# ProPrj_cyrus_2026-03-31.net
KiCad netlist of a schematic drawn in EasyEDA Pro
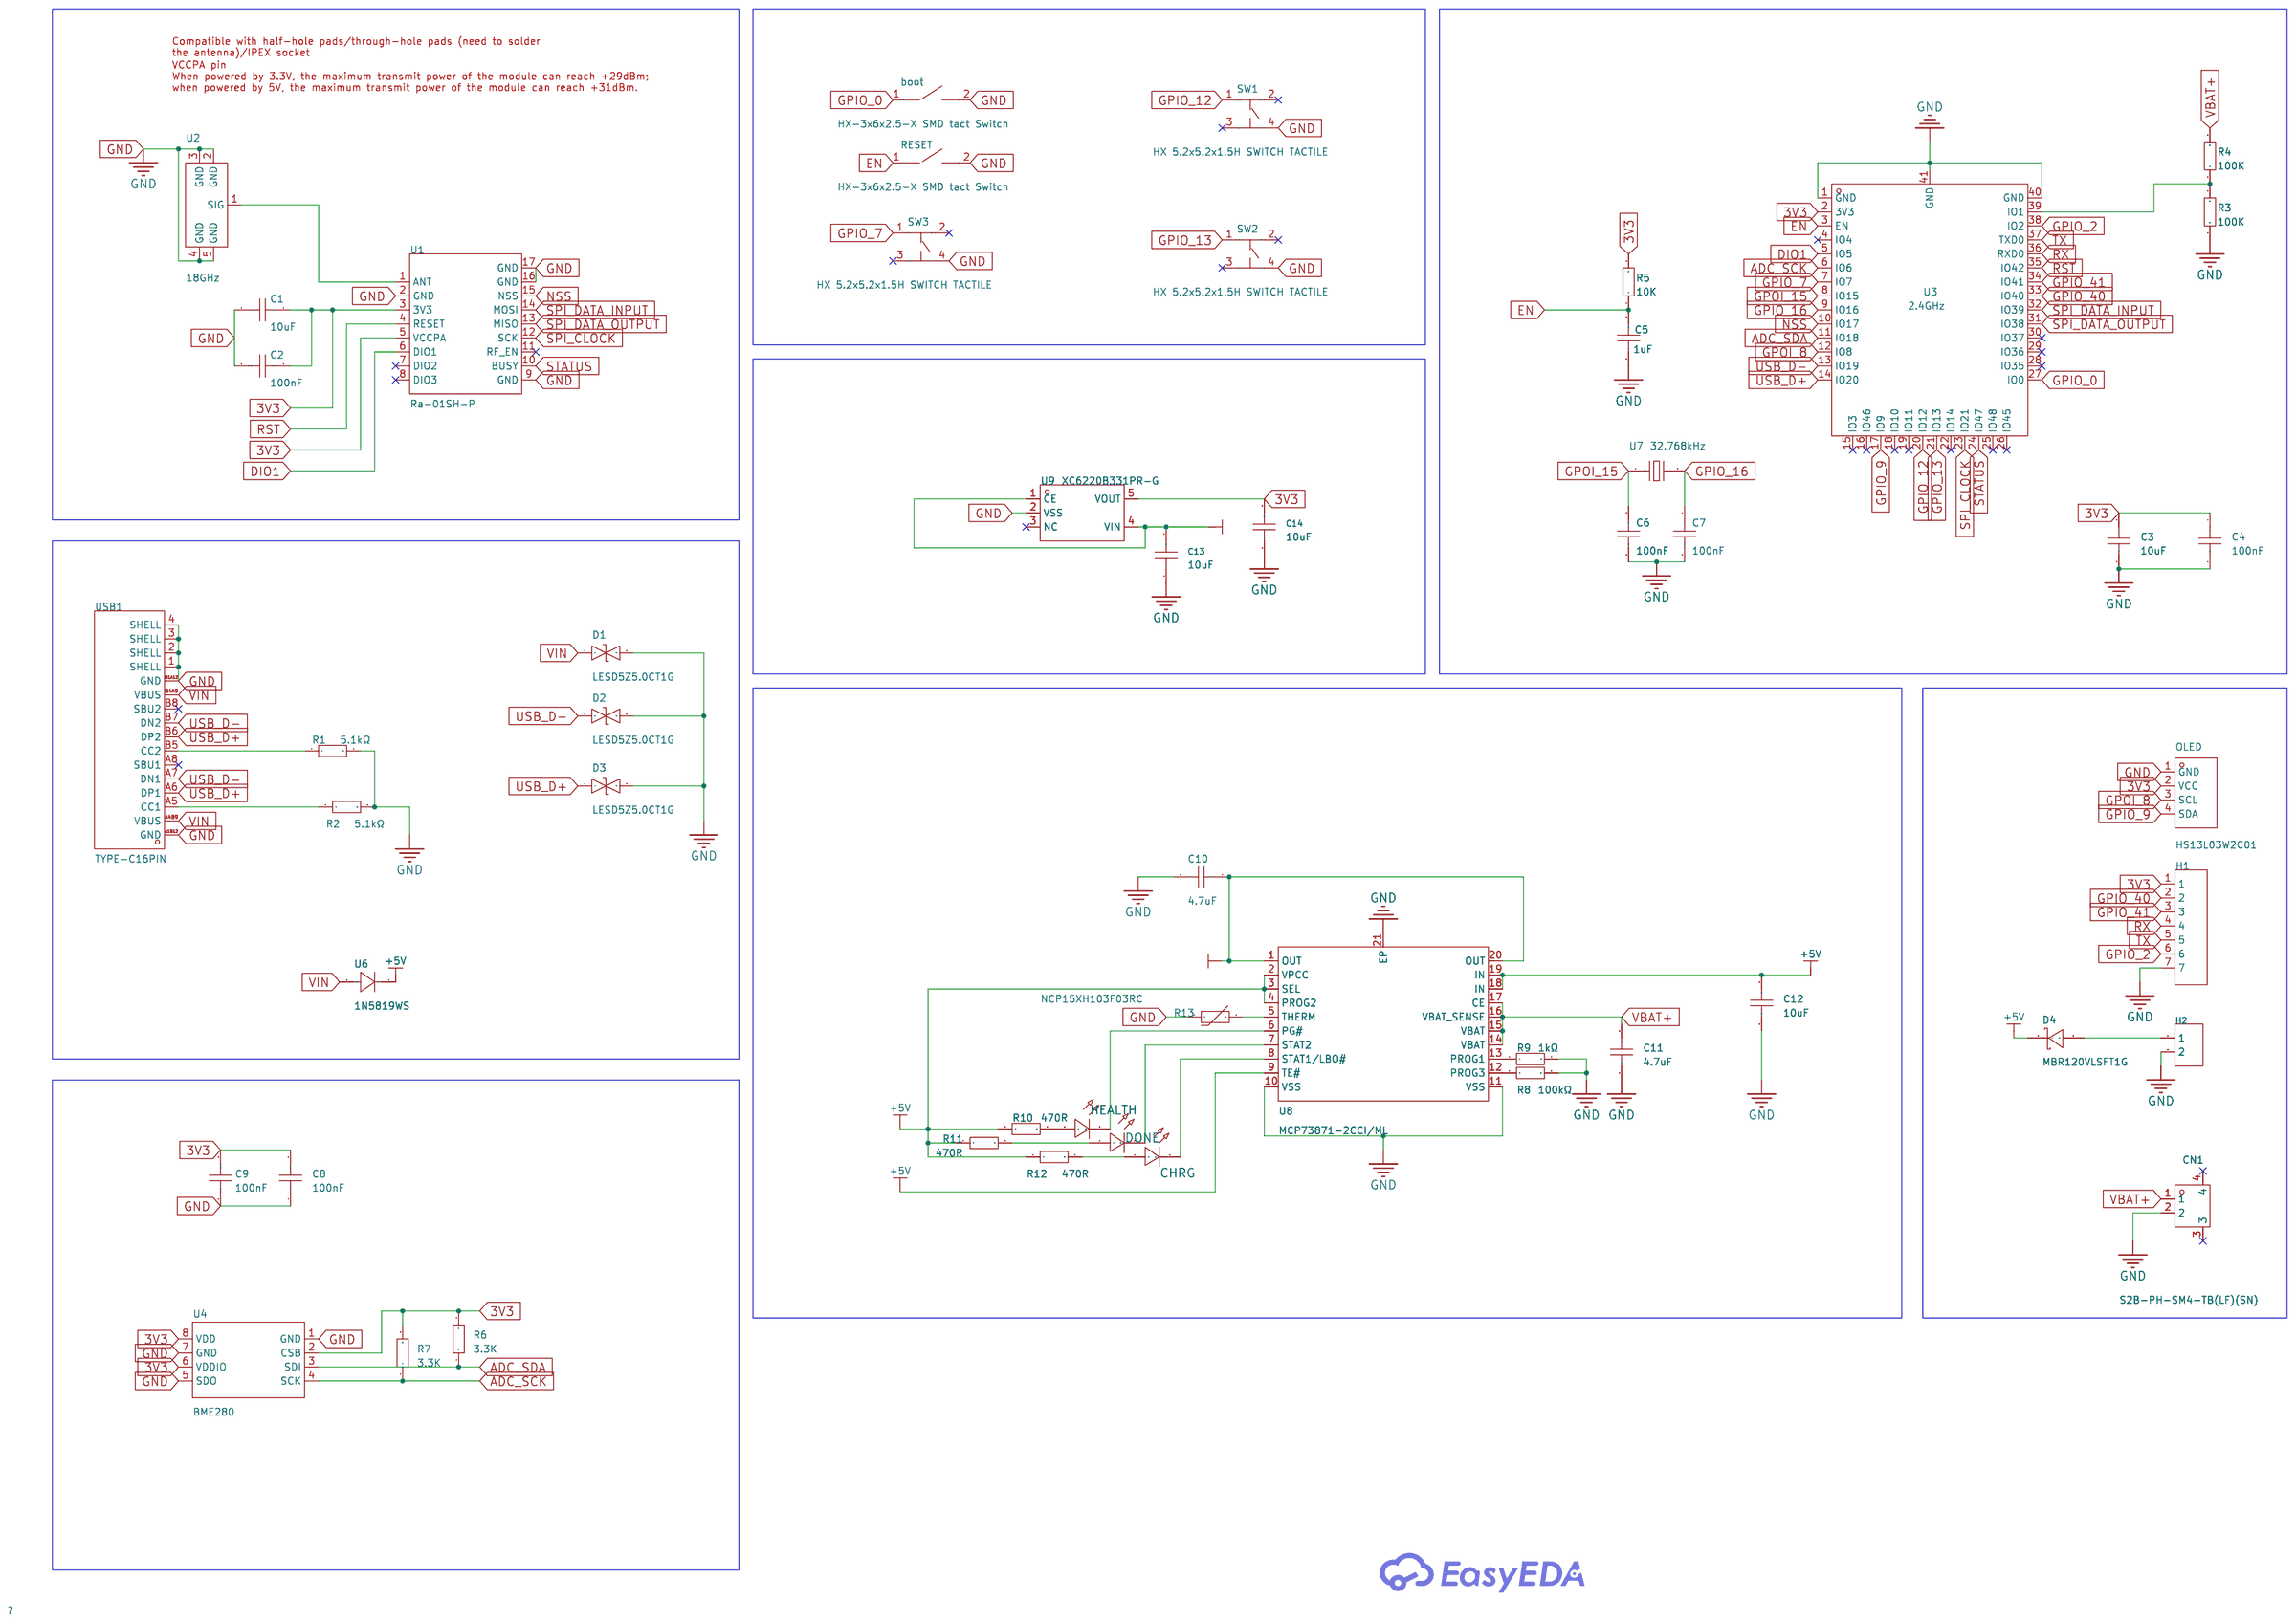
[diagram p0: schematic sheet]

(export (version "E")
  (design (tool "Eeschema 10.0.6"))
  (components
    (comp (ref "boot")
      (value "HX-3x6x2.5-X SMD tact Switch")
      (footprint "easyedapro:SW-SMD_HX-3X6X2.5-X")
      (fields (field (name "Manufacturer") "hanxia(韩下)"))
      (libsource (lib "easyedapro") (part "HX-3X6X2.5-X SMD TACT SWITCH"))
    )
    (comp (ref "C1")
      (value "10uF")
      (footprint "easyedapro:C0603")
      (libsource (lib "easyedapro") (part "CAP"))
    )
    (comp (ref "C2")
      (value "100nF")
      (footprint "easyedapro:C0603")
      (libsource (lib "easyedapro") (part "CAP"))
    )
    (comp (ref "C3")
      (value "10uF")
      (footprint "easyedapro:C0603")
      (libsource (lib "easyedapro") (part "CAP"))
    )
    (comp (ref "C4")
      (value "100nF")
      (footprint "easyedapro:C0603")
      (libsource (lib "easyedapro") (part "CAP"))
    )
    (comp (ref "C5") (value "1uF") (footprint "easyedapro:C0603") (libsource (lib "easyedapro") (part "CAP")))
    (comp (ref "C6")
      (value "100nF")
      (footprint "easyedapro:C0603")
      (libsource (lib "easyedapro") (part "CAP"))
    )
    (comp (ref "C7")
      (value "100nF")
      (footprint "easyedapro:C0603")
      (libsource (lib "easyedapro") (part "CAP"))
    )
    (comp (ref "C8")
      (value "100nF")
      (footprint "easyedapro:C0603")
      (description "Capacitance:100nF Tolerance:±10% Tolerance:±10% Voltage Rating:50V Temperature Coefficient:X7R")
      (fields
        (field (name "Manufacturer Part") "CC0603KRX7R9BB104")
        (field (name "Manufacturer") "YAGEO(国巨)")
      )
      (libsource (lib "easyedapro") (part "CC0603KRX7R9BB104"))
    )
    (comp (ref "C9")
      (value "100nF")
      (footprint "easyedapro:C0603")
      (description "Capacitance:100nF Tolerance:±10% Tolerance:±10% Voltage Rating:50V Temperature Coefficient:X7R")
      (fields
        (field (name "Manufacturer Part") "CC0603KRX7R9BB104")
        (field (name "Manufacturer") "YAGEO(国巨)")
      )
      (libsource (lib "easyedapro") (part "CC0603KRX7R9BB104"))
    )
    (comp (ref "C10")
      (value "4.7uF")
      (footprint "easyedapro:C0402")
      (description "Capacitance:4.7uF Tolerance:±20% Tolerance:±20% Voltage Rating:10V Temperature Coefficient:X5R")
      (fields
        (field (name "Manufacturer Part") "CL05A475MP5NRNC")
        (field (name "Manufacturer") "SAMSUNG(三星)")
      )
      (libsource (lib "easyedapro") (part "CL05A475MP5NRNC"))
    )
    (comp (ref "C11")
      (value "4.7uF")
      (footprint "easyedapro:C0402")
      (description "Capacitance:4.7uF Tolerance:±20% Tolerance:±20% Voltage Rating:10V Temperature Coefficient:X5R")
      (fields
        (field (name "Manufacturer Part") "CL05A475MP5NRNC")
        (field (name "Manufacturer") "SAMSUNG(三星)")
      )
      (libsource (lib "easyedapro") (part "CL05A475MP5NRNC"))
    )
    (comp (ref "C12")
      (value "10uF")
      (footprint "easyedapro:C0402")
      (description "Capacitance:10uF Tolerance:±20% Tolerance:±20% Voltage Rating:10V Temperature Coefficient:X5R")
      (fields
        (field (name "Manufacturer Part") "CL05A106MP5NUNC")
        (field (name "Manufacturer") "SAMSUNG(三星)")
      )
      (libsource (lib "easyedapro") (part "CL05A106MP5NUNC_C315248"))
    )
    (comp (ref "C13")
      (value "10uF")
      (footprint "easyedapro:C0603")
      (description "Capacitance:10uF Tolerance:±20% Tolerance:±20% Voltage Rating:25V Temperature Coefficient:X5R")
      (fields
        (field (name "Manufacturer Part") "CL10A106MA8NRNC")
        (field (name "Manufacturer") "SAMSUNG(三星)")
      )
      (libsource (lib "easyedapro") (part "CL10A106MA8NRNC"))
    )
    (comp (ref "C14")
      (value "10uF")
      (footprint "easyedapro:C0603")
      (description "Capacitance:10uF Tolerance:±20% Tolerance:±20% Voltage Rating:25V Temperature Coefficient:X5R")
      (fields
        (field (name "Manufacturer Part") "CL10A106MA8NRNC")
        (field (name "Manufacturer") "SAMSUNG(三星)")
      )
      (libsource (lib "easyedapro") (part "CL10A106MA8NRNC"))
    )
    (comp (ref "CHRG")
      (value "~")
      (footprint "easyedapro:LED0603-R-RD")
      (libsource (lib "easyedapro") (part "LED_R"))
    )
    (comp (ref "CN1")
      (value "S2B-PH-SM4-TB(LF)(SN)")
      (footprint "easyedapro:CONN-SMD_P2.00_S2B-PH-SM4-TB-LF-SN")
      (fields (field (name "Manufacturer") "JST"))
      (libsource (lib "easyedapro") (part "S2B-PH-SM4-TB(LF)(SN)"))
    )
    (comp (ref "D1")
      (value "LESD5Z5.0CT1G")
      (footprint "easyedapro:SOD-523_L1.2-W0.8-LS1.6-BI")
      (fields (field (name "Manufacturer") "LRC(乐山无线电)"))
      (libsource (lib "easyedapro") (part "LESD5Z5.0CT1G"))
    )
    (comp (ref "D2")
      (value "LESD5Z5.0CT1G")
      (footprint "easyedapro:SOD-523_L1.2-W0.8-LS1.6-BI")
      (fields (field (name "Manufacturer") "LRC(乐山无线电)"))
      (libsource (lib "easyedapro") (part "LESD5Z5.0CT1G"))
    )
    (comp (ref "D3")
      (value "LESD5Z5.0CT1G")
      (footprint "easyedapro:SOD-523_L1.2-W0.8-LS1.6-BI")
      (fields (field (name "Manufacturer") "LRC(乐山无线电)"))
      (libsource (lib "easyedapro") (part "LESD5Z5.0CT1G"))
    )
    (comp (ref "D4")
      (value "MBR120VLSFT1G")
      (footprint "easyedapro:SOD-123F_L2.8-W1.8-LS3.7-RD")
      (fields (field (name "Manufacturer") "onsemi(安森美)"))
      (libsource (lib "easyedapro") (part "MBR120VLSFT1G"))
    )
    (comp (ref "DONE")
      (value "~")
      (footprint "easyedapro:LED0603-R-RD")
      (libsource (lib "easyedapro") (part "LED_R"))
    )
    (comp (ref "H1")
      (value "~")
      (footprint "easyedapro:HDR-TH_7P-P2.54-V-F")
      (libsource (lib "easyedapro") (part "220S-1*7P H=8.5MM Ytype Gold-plated"))
    )
    (comp (ref "H2")
      (value "~")
      (footprint "easyedapro:HDR-TH_2P-P2.54-V-F")
      (libsource (lib "easyedapro") (part "Header-Female-2.54_1x2"))
    )
    (comp (ref "HEALTH")
      (value "~")
      (footprint "easyedapro:LED0603-R-RD")
      (libsource (lib "easyedapro") (part "LED_R"))
    )
    (comp (ref "OLED")
      (value "HS13L03W2C01")
      (footprint "easyedapro:OLED-TH_L35.4-W33.5_HS13L03W2C01")
      (fields (field (name "Manufacturer") "HS(汉昇)"))
      (libsource (lib "easyedapro") (part "HS13L03W2C01"))
    )
    (comp (ref "R1")
      (value "5.1kΩ")
      (footprint "easyedapro:R0603")
      (libsource (lib "easyedapro") (part "Res"))
    )
    (comp (ref "R2")
      (value "5.1kΩ")
      (footprint "easyedapro:R0603")
      (libsource (lib "easyedapro") (part "Res"))
    )
    (comp (ref "R3")
      (value "100K")
      (footprint "easyedapro:R0603")
      (libsource (lib "easyedapro") (part "Res"))
    )
    (comp (ref "R4")
      (value "100K")
      (footprint "easyedapro:R0603")
      (libsource (lib "easyedapro") (part "Res"))
    )
    (comp (ref "R5") (value "10K") (footprint "easyedapro:R0603") (libsource (lib "easyedapro") (part "Res")))
    (comp (ref "R6")
      (value "3.3K")
      (footprint "easyedapro:R0603")
      (libsource (lib "easyedapro") (part "Res"))
    )
    (comp (ref "R7")
      (value "3.3K")
      (footprint "easyedapro:R0603")
      (libsource (lib "easyedapro") (part "Res"))
    )
    (comp (ref "R8")
      (value "100kΩ")
      (footprint "easyedapro:R0603")
      (fields
        (field (name "Manufacturer Part") "0603WAF1003T5E")
        (field (name "Manufacturer") "UNI-ROYAL(厚声)")
      )
      (libsource (lib "easyedapro") (part "0603WAF1003T5E"))
    )
    (comp (ref "R9")
      (value "1kΩ")
      (footprint "easyedapro:R0402")
      (fields
        (field (name "Manufacturer Part") "0402WGF1001TCE")
        (field (name "Manufacturer") "UNI-ROYAL(厚声)")
      )
      (libsource (lib "easyedapro") (part "0402WGF1001TCE"))
    )
    (comp (ref "R10")
      (value "470R")
      (footprint "easyedapro:R0603")
      (libsource (lib "easyedapro") (part "Res"))
    )
    (comp (ref "R11")
      (value "470R")
      (footprint "easyedapro:R0603")
      (libsource (lib "easyedapro") (part "Res"))
    )
    (comp (ref "R12")
      (value "470R")
      (footprint "easyedapro:R0603")
      (libsource (lib "easyedapro") (part "Res"))
    )
    (comp (ref "R13")
      (value "NCP15XH103F03RC")
      (footprint "easyedapro:R0402")
      (fields (field (name "Manufacturer") "muRata(村田)"))
      (libsource (lib "easyedapro") (part "NCP15XH103F03RC"))
    )
    (comp (ref "RESET")
      (value "HX-3x6x2.5-X SMD tact Switch")
      (footprint "easyedapro:SW-SMD_HX-3X6X2.5-X")
      (fields (field (name "Manufacturer") "hanxia(韩下)"))
      (libsource (lib "easyedapro") (part "HX-3X6X2.5-X SMD TACT SWITCH"))
    )
    (comp (ref "SW1")
      (value "HX 5.2x5.2x1.5H SWITCH TACTILE")
      (footprint "easyedapro:SW-SMD_4P-L5.2-W5.2-P3.7-LS6.4-1")
      (fields (field (name "Manufacturer") "hanxia(韩下)"))
      (libsource (lib "easyedapro") (part "HX 5.2X5.2X1.5H SWITCH TACTILE"))
    )
    (comp (ref "SW2")
      (value "HX 5.2x5.2x1.5H SWITCH TACTILE")
      (footprint "easyedapro:SW-SMD_4P-L5.2-W5.2-P3.7-LS6.4-1")
      (fields (field (name "Manufacturer") "hanxia(韩下)"))
      (libsource (lib "easyedapro") (part "HX 5.2X5.2X1.5H SWITCH TACTILE"))
    )
    (comp (ref "SW3")
      (value "HX 5.2x5.2x1.5H SWITCH TACTILE")
      (footprint "easyedapro:SW-SMD_4P-L5.2-W5.2-P3.7-LS6.4-1")
      (fields (field (name "Manufacturer") "hanxia(韩下)"))
      (libsource (lib "easyedapro") (part "HX 5.2X5.2X1.5H SWITCH TACTILE"))
    )
    (comp (ref "U1")
      (value "Ra-01SH-P")
      (footprint "easyedapro:COMM-SMD_17P-L17.0-W16.0-P2.00_RA-01S-P")
      (fields (field (name "Manufacturer") "Ai-Thinker(安信可)"))
      (libsource (lib "easyedapro") (part "RA-01SH-P"))
    )
    (comp (ref "U2")
      (value "18GHz")
      (footprint "easyedapro:SMA-SMD_HJ-SMA076")
      (fields (field (name "Manufacturer Part") "142-0701-801") (field (name "Manufacturer") "belfuse"))
      (libsource (lib "easyedapro") (part "142-0701-801"))
    )
    (comp (ref "U3")
      (value "2.4GHz")
      (footprint "easyedapro:WIRELM-SMD_ESP32-S3-WROOM-1")
      (fields
        (field (name "Manufacturer Part") "ESP32-S3-WROOM-1-N8R8")
        (field (name "Manufacturer") "ESPRESSIF(乐鑫)")
      )
      (libsource (lib "easyedapro") (part "ESP32-S3-WROOM-1(N8R8)"))
    )
    (comp (ref "U4")
      (value "BME280")
      (footprint "easyedapro:LGA-8_BME280_BL")
      (fields (field (name "Manufacturer") "Bosch(博世)"))
      (libsource (lib "easyedapro") (part "BME280"))
    )
    (comp (ref "U6")
      (value "1N5819WS")
      (footprint "easyedapro:SOD-323_L1.8-W1.3-LS2.5-RD")
      (fields (field (name "Manufacturer") "HXY MOSFET(华轩阳电子)"))
      (libsource (lib "easyedapro") (part "1N5819WS_C5451629"))
    )
    (comp (ref "U7")
      (value "32.768kHz")
      (footprint "easyedapro:CRYSTAL-SMD_L3.2-W1.5-1")
      (fields (field (name "Manufacturer Part") "RN32768016") (field (name "Manufacturer") "TROQ(创捷)"))
      (libsource (lib "easyedapro") (part "RN32768016"))
    )
    (comp (ref "U8")
      (value "MCP73871-2CCI/ML")
      (footprint "easyedapro:QFN-20_L4.0-W4.0-P0.50-BL-EP2.7")
      (fields (field (name "Manufacturer") "MICROCHIP(美国微芯)"))
      (libsource (lib "easyedapro") (part "MCP73871-2CCI/ML"))
    )
    (comp (ref "U9")
      (value "XC6220B331PR-G")
      (footprint "easyedapro:SOT-89-5_L4.5-W2.5-P1.50-LS4.4-BR")
      (fields (field (name "Manufacturer") "TOREX(特瑞仕)"))
      (libsource (lib "easyedapro") (part "XC6220B331PR-G"))
    )
    (comp (ref "USB1")
      (value "TYPE-C16PIN")
      (footprint "easyedapro:USB-C-SMD_TYPE-C16PIN")
      (fields (field (name "Manufacturer") "SHOU HAN(首韩)"))
      (libsource (lib "easyedapro") (part "TYPE-C16PIN"))
    )
  )
  (nets
    (net (code "1") (name "+5V") (class "Default")
      (node (ref "C12") (pin "2") (pinfunction "2_2") (pintype "unspecified"))
      (node (ref "D4") (pin "1") (pinfunction "K_1") (pintype "unspecified"))
      (node (ref "R10") (pin "1") (pinfunction "1_1") (pintype "input"))
      (node (ref "R11") (pin "1") (pinfunction "1_1") (pintype "input"))
      (node (ref "R12") (pin "1") (pinfunction "1_1") (pintype "input"))
      (node (ref "U6") (pin "1") (pinfunction "K_1") (pintype "unspecified"))
      (node (ref "U8") (pin "18") (pinfunction "IN_18") (pintype "unspecified"))
      (node (ref "U8") (pin "19") (pinfunction "IN_19") (pintype "unspecified"))
      (node (ref "U8") (pin "2") (pinfunction "VPCC_2") (pintype "unspecified"))
      (node (ref "U8") (pin "3") (pinfunction "SEL_3") (pintype "unspecified"))
      (node (ref "U8") (pin "4") (pinfunction "PROG2_4") (pintype "unspecified"))
      (node (ref "U8") (pin "9") (pinfunction "TE#_9") (pintype "unspecified"))
    )
    (net (code "2") (name "3V3") (class "Default")
      (node (ref "C1") (pin "1") (pinfunction "1_1") (pintype "input"))
      (node (ref "C14") (pin "2") (pinfunction "2_2") (pintype "input"))
      (node (ref "C2") (pin "1") (pinfunction "1_1") (pintype "input"))
      (node (ref "C3") (pin "1") (pinfunction "1_1") (pintype "input"))
      (node (ref "C4") (pin "1") (pinfunction "1_1") (pintype "input"))
      (node (ref "C8") (pin "2") (pinfunction "2_2") (pintype "unspecified"))
      (node (ref "C9") (pin "2") (pinfunction "2_2") (pintype "unspecified"))
      (node (ref "H1") (pin "1") (pinfunction "1_1") (pintype "unspecified"))
      (node (ref "OLED") (pin "2") (pinfunction "VCC_2") (pintype "unspecified"))
      (node (ref "R5") (pin "2") (pinfunction "2_2") (pintype "input"))
      (node (ref "R6") (pin "2") (pinfunction "2_2") (pintype "input"))
      (node (ref "R7") (pin "2") (pinfunction "2_2") (pintype "input"))
      (node (ref "U1") (pin "3") (pinfunction "3V3_3") (pintype "unspecified"))
      (node (ref "U1") (pin "5") (pinfunction "VCCPA_5") (pintype "unspecified"))
      (node (ref "U3") (pin "2") (pinfunction "3V3_2") (pintype "unspecified"))
      (node (ref "U4") (pin "2") (pinfunction "CSB_2") (pintype "unspecified"))
      (node (ref "U4") (pin "6") (pinfunction "VDDIO_6") (pintype "unspecified"))
      (node (ref "U4") (pin "8") (pinfunction "VDD_8") (pintype "unspecified"))
      (node (ref "U9") (pin "5") (pinfunction "VOUT_5") (pintype "unspecified"))
    )
    (net (code "3") (name "ADC_SCK") (class "Default")
      (node (ref "R7") (pin "1") (pinfunction "1_1") (pintype "input"))
      (node (ref "U3") (pin "6") (pinfunction "IO6_6") (pintype "unspecified"))
      (node (ref "U4") (pin "4") (pinfunction "SCK_4") (pintype "unspecified"))
    )
    (net (code "4") (name "ADC_SDA") (class "Default")
      (node (ref "R6") (pin "1") (pinfunction "1_1") (pintype "input"))
      (node (ref "U3") (pin "11") (pinfunction "IO18_11") (pintype "unspecified"))
      (node (ref "U4") (pin "3") (pinfunction "SDI_3") (pintype "unspecified"))
    )
    (net (code "5") (name "DIO1") (class "Default")
      (node (ref "U1") (pin "6") (pinfunction "DIO1_6") (pintype "unspecified"))
      (node (ref "U3") (pin "5") (pinfunction "IO5_5") (pintype "unspecified"))
    )
    (net (code "6") (name "EN") (class "Default")
      (node (ref "C5") (pin "1") (pinfunction "1_1") (pintype "input"))
      (node (ref "R5") (pin "1") (pinfunction "1_1") (pintype "input"))
      (node (ref "RESET") (pin "1") (pinfunction "1_1") (pintype "unspecified"))
      (node (ref "U3") (pin "3") (pinfunction "EN_3") (pintype "unspecified"))
    )
    (net (code "7") (name "GND") (class "Default")
      (node (ref "C1") (pin "2") (pinfunction "2_2") (pintype "input"))
      (node (ref "C10") (pin "1") (pinfunction "1_1") (pintype "unspecified"))
      (node (ref "C11") (pin "1") (pinfunction "1_1") (pintype "unspecified"))
      (node (ref "C12") (pin "1") (pinfunction "1_1") (pintype "unspecified"))
      (node (ref "C13") (pin "1") (pinfunction "1_1") (pintype "input"))
      (node (ref "C14") (pin "1") (pinfunction "1_1") (pintype "input"))
      (node (ref "C2") (pin "2") (pinfunction "2_2") (pintype "input"))
      (node (ref "C3") (pin "2") (pinfunction "2_2") (pintype "input"))
      (node (ref "C4") (pin "2") (pinfunction "2_2") (pintype "input"))
      (node (ref "C5") (pin "2") (pinfunction "2_2") (pintype "input"))
      (node (ref "C6") (pin "2") (pinfunction "2_2") (pintype "input"))
      (node (ref "C7") (pin "2") (pinfunction "2_2") (pintype "input"))
      (node (ref "C8") (pin "1") (pinfunction "1_1") (pintype "unspecified"))
      (node (ref "C9") (pin "1") (pinfunction "1_1") (pintype "unspecified"))
      (node (ref "CN1") (pin "2") (pinfunction "2_2") (pintype "unspecified"))
      (node (ref "D1") (pin "2") (pinfunction "2_2") (pintype "unspecified"))
      (node (ref "D2") (pin "2") (pinfunction "2_2") (pintype "unspecified"))
      (node (ref "D3") (pin "2") (pinfunction "2_2") (pintype "unspecified"))
      (node (ref "H1") (pin "7") (pinfunction "7_7") (pintype "unspecified"))
      (node (ref "H2") (pin "2") (pinfunction "2_2") (pintype "input"))
      (node (ref "OLED") (pin "1") (pinfunction "GND_1") (pintype "unspecified"))
      (node (ref "R1") (pin "2") (pinfunction "2_2") (pintype "input"))
      (node (ref "R13") (pin "1") (pinfunction "1_1") (pintype "input"))
      (node (ref "R2") (pin "2") (pinfunction "2_2") (pintype "input"))
      (node (ref "R3") (pin "1") (pinfunction "1_1") (pintype "input"))
      (node (ref "R8") (pin "2") (pinfunction "2_2") (pintype "input"))
      (node (ref "R9") (pin "2") (pinfunction "2_2") (pintype "input"))
      (node (ref "RESET") (pin "2") (pinfunction "2_2") (pintype "unspecified"))
      (node (ref "SW1") (pin "4") (pinfunction "4_4") (pintype "unspecified"))
      (node (ref "SW2") (pin "4") (pinfunction "4_4") (pintype "unspecified"))
      (node (ref "SW3") (pin "4") (pinfunction "4_4") (pintype "unspecified"))
      (node (ref "U1") (pin "16") (pinfunction "GND_16") (pintype "unspecified"))
      (node (ref "U1") (pin "17") (pinfunction "GND_17") (pintype "unspecified"))
      (node (ref "U1") (pin "2") (pinfunction "GND_2") (pintype "unspecified"))
      (node (ref "U1") (pin "9") (pinfunction "GND_9") (pintype "unspecified"))
      (node (ref "U2") (pin "2") (pinfunction "GND_2") (pintype "unspecified"))
      (node (ref "U2") (pin "3") (pinfunction "GND_3") (pintype "unspecified"))
      (node (ref "U2") (pin "4") (pinfunction "GND_4") (pintype "unspecified"))
      (node (ref "U2") (pin "5") (pinfunction "GND_5") (pintype "unspecified"))
      (node (ref "U3") (pin "1") (pinfunction "GND_1") (pintype "unspecified"))
      (node (ref "U3") (pin "40") (pinfunction "GND_40") (pintype "unspecified"))
      (node (ref "U3") (pin "41") (pinfunction "GND_41") (pintype "unspecified"))
      (node (ref "U4") (pin "1") (pinfunction "GND_1") (pintype "unspecified"))
      (node (ref "U4") (pin "5") (pinfunction "SDO_5") (pintype "unspecified"))
      (node (ref "U4") (pin "7") (pinfunction "GND_7") (pintype "unspecified"))
      (node (ref "U8") (pin "10") (pinfunction "VSS_10") (pintype "unspecified"))
      (node (ref "U8") (pin "11") (pinfunction "VSS_11") (pintype "unspecified"))
      (node (ref "U8") (pin "21") (pinfunction "EP_21") (pintype "unspecified"))
      (node (ref "U9") (pin "2") (pinfunction "VSS_2") (pintype "unspecified"))
      (node (ref "USB1") (pin "1") (pinfunction "SHELL_1") (pintype "unspecified"))
      (node (ref "USB1") (pin "2") (pinfunction "SHELL_2") (pintype "unspecified"))
      (node (ref "USB1") (pin "3") (pinfunction "SHELL_3") (pintype "unspecified"))
      (node (ref "USB1") (pin "4") (pinfunction "SHELL_4") (pintype "unspecified"))
      (node (ref "USB1") (pin "A1B12") (pinfunction "GND_A1B12") (pintype "unspecified"))
      (node (ref "USB1") (pin "B1A12") (pinfunction "GND_B1A12") (pintype "unspecified"))
      (node (ref "boot") (pin "2") (pinfunction "2_2") (pintype "unspecified"))
    )
    (net (code "8") (name "GPIO_0") (class "Default")
      (node (ref "U3") (pin "27") (pinfunction "IO0_27") (pintype "unspecified"))
      (node (ref "boot") (pin "1") (pinfunction "1_1") (pintype "unspecified"))
    )
    (net (code "9") (name "GPIO_2") (class "Default")
      (node (ref "H1") (pin "6") (pinfunction "6_6") (pintype "unspecified"))
      (node (ref "U3") (pin "38") (pinfunction "IO2_38") (pintype "unspecified"))
    )
    (net (code "10") (name "GPIO_7") (class "Default")
      (node (ref "SW3") (pin "1") (pinfunction "1_1") (pintype "unspecified"))
      (node (ref "U3") (pin "7") (pinfunction "IO7_7") (pintype "unspecified"))
    )
    (net (code "11") (name "GPIO_9") (class "Default")
      (node (ref "OLED") (pin "4") (pinfunction "SDA_4") (pintype "unspecified"))
      (node (ref "U3") (pin "17") (pinfunction "IO9_17") (pintype "unspecified"))
    )
    (net (code "12") (name "GPIO_12") (class "Default")
      (node (ref "SW1") (pin "1") (pinfunction "1_1") (pintype "unspecified"))
      (node (ref "U3") (pin "20") (pinfunction "IO12_20") (pintype "unspecified"))
    )
    (net (code "13") (name "GPIO_13") (class "Default")
      (node (ref "SW2") (pin "1") (pinfunction "1_1") (pintype "unspecified"))
      (node (ref "U3") (pin "21") (pinfunction "IO13_21") (pintype "unspecified"))
    )
    (net (code "14") (name "GPIO_16") (class "Default")
      (node (ref "C7") (pin "1") (pinfunction "1_1") (pintype "input"))
      (node (ref "U3") (pin "9") (pinfunction "IO16_9") (pintype "unspecified"))
      (node (ref "U7") (pin "2") (pinfunction "2_2") (pintype "input"))
    )
    (net (code "15") (name "GPIO_40") (class "Default")
      (node (ref "H1") (pin "2") (pinfunction "2_2") (pintype "unspecified"))
      (node (ref "U3") (pin "33") (pinfunction "IO40_33") (pintype "unspecified"))
    )
    (net (code "16") (name "GPIO_41") (class "Default")
      (node (ref "H1") (pin "3") (pinfunction "3_3") (pintype "unspecified"))
      (node (ref "U3") (pin "34") (pinfunction "IO41_34") (pintype "unspecified"))
    )
    (net (code "17") (name "GPOI_8") (class "Default")
      (node (ref "OLED") (pin "3") (pinfunction "SCL_3") (pintype "unspecified"))
      (node (ref "U3") (pin "12") (pinfunction "IO8_12") (pintype "unspecified"))
    )
    (net (code "18") (name "GPOI_15") (class "Default")
      (node (ref "C6") (pin "1") (pinfunction "1_1") (pintype "input"))
      (node (ref "U3") (pin "8") (pinfunction "IO15_8") (pintype "unspecified"))
      (node (ref "U7") (pin "1") (pinfunction "1_1") (pintype "input"))
    )
    (net (code "19") (name "NSS") (class "Default")
      (node (ref "U1") (pin "15") (pinfunction "NSS_15") (pintype "unspecified"))
      (node (ref "U3") (pin "10") (pinfunction "IO17_10") (pintype "unspecified"))
    )
    (net (code "20") (name "Net-(CHRG-A)") (class "Default")
      (node (ref "CHRG") (pin "1") (pinfunction "A_1") (pintype "input"))
      (node (ref "R12") (pin "2") (pinfunction "2_2") (pintype "input"))
    )
    (net (code "21") (name "Net-(CHRG-C)") (class "Default")
      (node (ref "CHRG") (pin "2") (pinfunction "C_2") (pintype "input"))
      (node (ref "U8") (pin "8") (pinfunction "STAT1/LBO#_8") (pintype "unspecified"))
    )
    (net (code "22") (name "Net-(D4-A)") (class "Default")
      (node (ref "D4") (pin "2") (pinfunction "A_2") (pintype "unspecified"))
      (node (ref "H2") (pin "1") (pinfunction "1_1") (pintype "input"))
    )
    (net (code "23") (name "Net-(DONE-A)") (class "Default")
      (node (ref "DONE") (pin "1") (pinfunction "A_1") (pintype "input"))
      (node (ref "R11") (pin "2") (pinfunction "2_2") (pintype "input"))
    )
    (net (code "24") (name "Net-(DONE-C)") (class "Default")
      (node (ref "DONE") (pin "2") (pinfunction "C_2") (pintype "input"))
      (node (ref "U8") (pin "7") (pinfunction "STAT2_7") (pintype "unspecified"))
    )
    (net (code "25") (name "Net-(HEALTH-A)") (class "Default")
      (node (ref "HEALTH") (pin "1") (pinfunction "A_1") (pintype "input"))
      (node (ref "R10") (pin "2") (pinfunction "2_2") (pintype "input"))
    )
    (net (code "26") (name "Net-(HEALTH-C)") (class "Default")
      (node (ref "HEALTH") (pin "2") (pinfunction "C_2") (pintype "input"))
      (node (ref "U8") (pin "6") (pinfunction "PG#_6") (pintype "unspecified"))
    )
    (net (code "27") (name "Net-(U1-ANT)") (class "Default")
      (node (ref "U1") (pin "1") (pinfunction "ANT_1") (pintype "unspecified"))
      (node (ref "U2") (pin "1") (pinfunction "SIG_1") (pintype "unspecified"))
    )
    (net (code "28") (name "Net-(U3-IO1)") (class "Default")
      (node (ref "R3") (pin "2") (pinfunction "2_2") (pintype "input"))
      (node (ref "R4") (pin "1") (pinfunction "1_1") (pintype "input"))
      (node (ref "U3") (pin "39") (pinfunction "IO1_39") (pintype "unspecified"))
    )
    (net (code "29") (name "Net-(U8-PROG1)") (class "Default")
      (node (ref "R9") (pin "1") (pinfunction "1_1") (pintype "input"))
      (node (ref "U8") (pin "13") (pinfunction "PROG1_13") (pintype "unspecified"))
    )
    (net (code "30") (name "Net-(U8-PROG3)") (class "Default")
      (node (ref "R8") (pin "1") (pinfunction "1_1") (pintype "input"))
      (node (ref "U8") (pin "12") (pinfunction "PROG3_12") (pintype "unspecified"))
    )
    (net (code "31") (name "Net-(U8-THERM)") (class "Default")
      (node (ref "R13") (pin "2") (pinfunction "2_2") (pintype "input"))
      (node (ref "U8") (pin "5") (pinfunction "THERM_5") (pintype "unspecified"))
    )
    (net (code "32") (name "Net-(USB1-CC1)") (class "Default")
      (node (ref "R2") (pin "1") (pinfunction "1_1") (pintype "input"))
      (node (ref "USB1") (pin "A5") (pinfunction "CC1_A5") (pintype "unspecified"))
    )
    (net (code "33") (name "Net-(USB1-CC2)") (class "Default")
      (node (ref "R1") (pin "1") (pinfunction "1_1") (pintype "input"))
      (node (ref "USB1") (pin "B5") (pinfunction "CC2_B5") (pintype "unspecified"))
    )
    (net (code "34") (name "RST") (class "Default")
      (node (ref "U1") (pin "4") (pinfunction "RESET_4") (pintype "unspecified"))
      (node (ref "U3") (pin "35") (pinfunction "IO42_35") (pintype "unspecified"))
    )
    (net (code "35") (name "RX") (class "Default")
      (node (ref "H1") (pin "4") (pinfunction "4_4") (pintype "unspecified"))
      (node (ref "U3") (pin "36") (pinfunction "RXD0_36") (pintype "unspecified"))
    )
    (net (code "36") (name "SPI_CLOCK") (class "Default")
      (node (ref "U1") (pin "12") (pinfunction "SCK_12") (pintype "unspecified"))
      (node (ref "U3") (pin "23") (pinfunction "IO21_23") (pintype "unspecified"))
    )
    (net (code "37") (name "SPI_DATA_INPUT") (class "Default")
      (node (ref "U1") (pin "14") (pinfunction "MOSI_14") (pintype "unspecified"))
      (node (ref "U3") (pin "32") (pinfunction "IO39_32") (pintype "unspecified"))
    )
    (net (code "38") (name "SPI_DATA_OUTPUT") (class "Default")
      (node (ref "U1") (pin "13") (pinfunction "MISO_13") (pintype "unspecified"))
      (node (ref "U3") (pin "31") (pinfunction "IO38_31") (pintype "unspecified"))
    )
    (net (code "39") (name "STATUS") (class "Default")
      (node (ref "U1") (pin "10") (pinfunction "BUSY_10") (pintype "unspecified"))
      (node (ref "U3") (pin "24") (pinfunction "IO47_24") (pintype "unspecified"))
    )
    (net (code "40") (name "TX") (class "Default")
      (node (ref "H1") (pin "5") (pinfunction "5_5") (pintype "unspecified"))
      (node (ref "U3") (pin "37") (pinfunction "TXD0_37") (pintype "unspecified"))
    )
    (net (code "41") (name "USB_D+") (class "Default")
      (node (ref "D3") (pin "1") (pinfunction "1_1") (pintype "unspecified"))
      (node (ref "U3") (pin "14") (pinfunction "IO20_14") (pintype "unspecified"))
      (node (ref "USB1") (pin "A6") (pinfunction "DP1_A6") (pintype "unspecified"))
      (node (ref "USB1") (pin "B6") (pinfunction "DP2_B6") (pintype "unspecified"))
    )
    (net (code "42") (name "USB_D-") (class "Default")
      (node (ref "D2") (pin "1") (pinfunction "1_1") (pintype "unspecified"))
      (node (ref "U3") (pin "13") (pinfunction "IO19_13") (pintype "unspecified"))
      (node (ref "USB1") (pin "A7") (pinfunction "DN1_A7") (pintype "unspecified"))
      (node (ref "USB1") (pin "B7") (pinfunction "DN2_B7") (pintype "unspecified"))
    )
    (net (code "43") (name "VBAT+") (class "Default")
      (node (ref "C11") (pin "2") (pinfunction "2_2") (pintype "unspecified"))
      (node (ref "CN1") (pin "1") (pinfunction "1_1") (pintype "unspecified"))
      (node (ref "R4") (pin "2") (pinfunction "2_2") (pintype "input"))
      (node (ref "U8") (pin "14") (pinfunction "VBAT_14") (pintype "unspecified"))
      (node (ref "U8") (pin "15") (pinfunction "VBAT_15") (pintype "unspecified"))
      (node (ref "U8") (pin "16") (pinfunction "VBAT_SENSE_16") (pintype "unspecified"))
      (node (ref "U8") (pin "17") (pinfunction "CE_17") (pintype "unspecified"))
    )
    (net (code "44") (name "VIN") (class "Default")
      (node (ref "D1") (pin "1") (pinfunction "1_1") (pintype "unspecified"))
      (node (ref "U6") (pin "2") (pinfunction "A_2") (pintype "unspecified"))
      (node (ref "USB1") (pin "A4B9") (pinfunction "VBUS_A4B9") (pintype "unspecified"))
      (node (ref "USB1") (pin "B4A9") (pinfunction "VBUS_B4A9") (pintype "unspecified"))
    )
    (net (code "45") (name "VSYS") (class "Default")
      (node (ref "C10") (pin "2") (pinfunction "2_2") (pintype "unspecified"))
      (node (ref "C13") (pin "2") (pinfunction "2_2") (pintype "input"))
      (node (ref "U8") (pin "1") (pinfunction "OUT_1") (pintype "unspecified"))
      (node (ref "U8") (pin "20") (pinfunction "OUT_20") (pintype "unspecified"))
      (node (ref "U9") (pin "1") (pinfunction "CE_1") (pintype "unspecified"))
      (node (ref "U9") (pin "4") (pinfunction "VIN_4") (pintype "unspecified"))
    )
    (net (code "46") (name "unconnected-(CN1-Pad3)") (class "Default")
      (node (ref "CN1") (pin "3") (pinfunction "3_3") (pintype "unspecified+no_connect"))
    )
    (net (code "47") (name "unconnected-(CN1-Pad4)") (class "Default")
      (node (ref "CN1") (pin "4") (pinfunction "4_4") (pintype "unspecified+no_connect"))
    )
    (net (code "48") (name "unconnected-(SW1-Pad2)") (class "Default")
      (node (ref "SW1") (pin "2") (pinfunction "2_2") (pintype "unspecified+no_connect"))
    )
    (net (code "49") (name "unconnected-(SW1-Pad3)") (class "Default")
      (node (ref "SW1") (pin "3") (pinfunction "3_3") (pintype "unspecified+no_connect"))
    )
    (net (code "50") (name "unconnected-(SW2-Pad2)") (class "Default")
      (node (ref "SW2") (pin "2") (pinfunction "2_2") (pintype "unspecified+no_connect"))
    )
    (net (code "51") (name "unconnected-(SW2-Pad3)") (class "Default")
      (node (ref "SW2") (pin "3") (pinfunction "3_3") (pintype "unspecified+no_connect"))
    )
    (net (code "52") (name "unconnected-(SW3-Pad2)") (class "Default")
      (node (ref "SW3") (pin "2") (pinfunction "2_2") (pintype "unspecified+no_connect"))
    )
    (net (code "53") (name "unconnected-(SW3-Pad3)") (class "Default")
      (node (ref "SW3") (pin "3") (pinfunction "3_3") (pintype "unspecified+no_connect"))
    )
    (net (code "54") (name "unconnected-(U1-DIO2-Pad7)") (class "Default")
      (node (ref "U1") (pin "7") (pinfunction "DIO2_7") (pintype "unspecified+no_connect"))
    )
    (net (code "55") (name "unconnected-(U1-DIO3-Pad8)") (class "Default")
      (node (ref "U1") (pin "8") (pinfunction "DIO3_8") (pintype "unspecified+no_connect"))
    )
    (net (code "56") (name "unconnected-(U1-RF_EN-Pad11)") (class "Default")
      (node (ref "U1") (pin "11") (pinfunction "RF_EN_11") (pintype "unspecified+no_connect"))
    )
    (net (code "57") (name "unconnected-(U3-IO3-Pad15)") (class "Default")
      (node (ref "U3") (pin "15") (pinfunction "IO3_15") (pintype "unspecified+no_connect"))
    )
    (net (code "58") (name "unconnected-(U3-IO4-Pad4)") (class "Default")
      (node (ref "U3") (pin "4") (pinfunction "IO4_4") (pintype "unspecified+no_connect"))
    )
    (net (code "59") (name "unconnected-(U3-IO10-Pad18)") (class "Default")
      (node (ref "U3") (pin "18") (pinfunction "IO10_18") (pintype "unspecified+no_connect"))
    )
    (net (code "60") (name "unconnected-(U3-IO11-Pad19)") (class "Default")
      (node (ref "U3") (pin "19") (pinfunction "IO11_19") (pintype "unspecified+no_connect"))
    )
    (net (code "61") (name "unconnected-(U3-IO14-Pad22)") (class "Default")
      (node (ref "U3") (pin "22") (pinfunction "IO14_22") (pintype "unspecified+no_connect"))
    )
    (net (code "62") (name "unconnected-(U3-IO35-Pad28)") (class "Default")
      (node (ref "U3") (pin "28") (pinfunction "IO35_28") (pintype "unspecified+no_connect"))
    )
    (net (code "63") (name "unconnected-(U3-IO36-Pad29)") (class "Default")
      (node (ref "U3") (pin "29") (pinfunction "IO36_29") (pintype "unspecified+no_connect"))
    )
    (net (code "64") (name "unconnected-(U3-IO37-Pad30)") (class "Default")
      (node (ref "U3") (pin "30") (pinfunction "IO37_30") (pintype "unspecified+no_connect"))
    )
    (net (code "65") (name "unconnected-(U3-IO45-Pad26)") (class "Default")
      (node (ref "U3") (pin "26") (pinfunction "IO45_26") (pintype "unspecified+no_connect"))
    )
    (net (code "66") (name "unconnected-(U3-IO46-Pad16)") (class "Default")
      (node (ref "U3") (pin "16") (pinfunction "IO46_16") (pintype "unspecified+no_connect"))
    )
    (net (code "67") (name "unconnected-(U3-IO48-Pad25)") (class "Default")
      (node (ref "U3") (pin "25") (pinfunction "IO48_25") (pintype "unspecified+no_connect"))
    )
    (net (code "68") (name "unconnected-(U9-NC-Pad3)") (class "Default")
      (node (ref "U9") (pin "3") (pinfunction "NC_3") (pintype "unspecified+no_connect"))
    )
    (net (code "69") (name "unconnected-(USB1-SBU1-PadA8)") (class "Default")
      (node (ref "USB1") (pin "A8") (pinfunction "SBU1_A8") (pintype "unspecified+no_connect"))
    )
    (net (code "70") (name "unconnected-(USB1-SBU2-PadB8)") (class "Default")
      (node (ref "USB1") (pin "B8") (pinfunction "SBU2_B8") (pintype "unspecified+no_connect"))
    )
  )
)
